# gelh.net
KiCad netlist of a schematic drawn in EAGLE
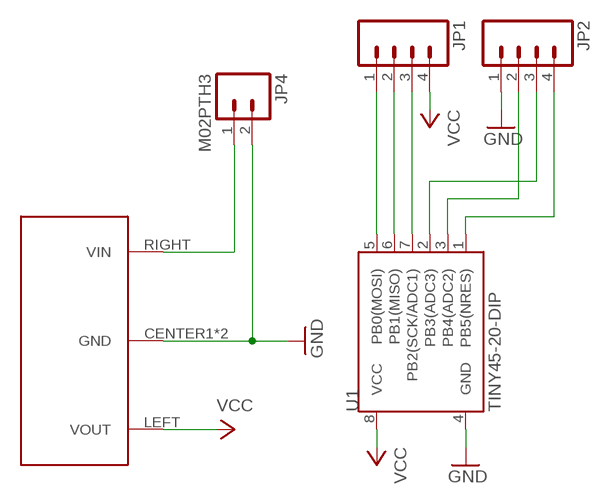
[diagram p0: schematic, sheet 1]

(export (version "E")
  (design (tool "Eeschema 10.0.6"))
  (components
    (comp (ref "JP1")
      (value "M04LONGPADS")
      (footprint "eagle-import:1X04_LONGPADS")
      (libsource (lib "eagle-import") (part "M04LONGPADS"))
    )
    (comp (ref "JP2")
      (value "M04LONGPADS")
      (footprint "eagle-import:1X04_LONGPADS")
      (libsource (lib "eagle-import") (part "M04LONGPADS"))
    )
    (comp (ref "JP4")
      (value "M02PTH3")
      (footprint "eagle-import:1X02_LONGPADS")
      (libsource (lib "eagle-import") (part "M02PTH3"))
    )
    (comp (ref "U$1")
      (value "78L05")
      (footprint "eagle-import:SOT89")
      (libsource (lib "eagle-import") (part "78L05"))
    )
    (comp (ref "U1")
      (value "TINY45-20-DIP")
      (footprint "eagle-import:DIP08")
      (libsource (lib "eagle-import") (part "ATTINY45TINY45-20-DIP"))
    )
  )
  (nets
    (net (code "1") (name "GND") (class "Default")
      (node (ref "JP2") (pin "1") (pinfunction "1_1") (pintype "passive"))
      (node (ref "JP4") (pin "2") (pinfunction "2_2") (pintype "passive"))
      (node (ref "U$1") (pin "CENTER1") (pinfunction "GND_CENTER1") (pintype "bidirectional"))
      (node (ref "U$1") (pin "CENTER2") (pinfunction "GND_CENTER2") (pintype "bidirectional"))
      (node (ref "U1") (pin "4") (pinfunction "GND_4") (pintype "bidirectional"))
    )
    (net (code "2") (name "Net-(U$1-VIN)") (class "Default")
      (node (ref "JP4") (pin "1") (pinfunction "1_1") (pintype "passive"))
      (node (ref "U$1") (pin "RIGHT") (pinfunction "VIN_RIGHT") (pintype "bidirectional"))
    )
    (net (code "3") (name "Net-(U1-PB0(MOSI))") (class "Default")
      (node (ref "JP1") (pin "1") (pinfunction "1_1") (pintype "passive"))
      (node (ref "U1") (pin "5") (pinfunction "PB0(MOSI)_5") (pintype "bidirectional"))
    )
    (net (code "4") (name "Net-(U1-PB1(MISO))") (class "Default")
      (node (ref "JP1") (pin "2") (pinfunction "2_2") (pintype "passive"))
      (node (ref "U1") (pin "6") (pinfunction "PB1(MISO)_6") (pintype "bidirectional"))
    )
    (net (code "5") (name "Net-(U1-PB2(SCK{slash}ADC1))") (class "Default")
      (node (ref "JP1") (pin "3") (pinfunction "3_3") (pintype "passive"))
      (node (ref "U1") (pin "7") (pinfunction "PB2(SCK/ADC1)_7") (pintype "bidirectional"))
    )
    (net (code "6") (name "Net-(U1-PB3(ADC3))") (class "Default")
      (node (ref "JP2") (pin "3") (pinfunction "3_3") (pintype "passive"))
      (node (ref "U1") (pin "2") (pinfunction "PB3(ADC3)_2") (pintype "bidirectional"))
    )
    (net (code "7") (name "Net-(U1-PB4(ADC2))") (class "Default")
      (node (ref "JP2") (pin "2") (pinfunction "2_2") (pintype "passive"))
      (node (ref "U1") (pin "3") (pinfunction "PB4(ADC2)_3") (pintype "bidirectional"))
    )
    (net (code "8") (name "Net-(U1-PB5(NRES))") (class "Default")
      (node (ref "JP2") (pin "4") (pinfunction "4_4") (pintype "passive"))
      (node (ref "U1") (pin "1") (pinfunction "PB5(NRES)_1") (pintype "bidirectional"))
    )
    (net (code "9") (name "VCC") (class "Default")
      (node (ref "JP1") (pin "4") (pinfunction "4_4") (pintype "passive"))
      (node (ref "U$1") (pin "LEFT") (pinfunction "VOUT_LEFT") (pintype "bidirectional"))
      (node (ref "U1") (pin "8") (pinfunction "VCC_8") (pintype "bidirectional"))
    )
  )
)
